# control.net
KiCad netlist of a schematic drawn in EAGLE
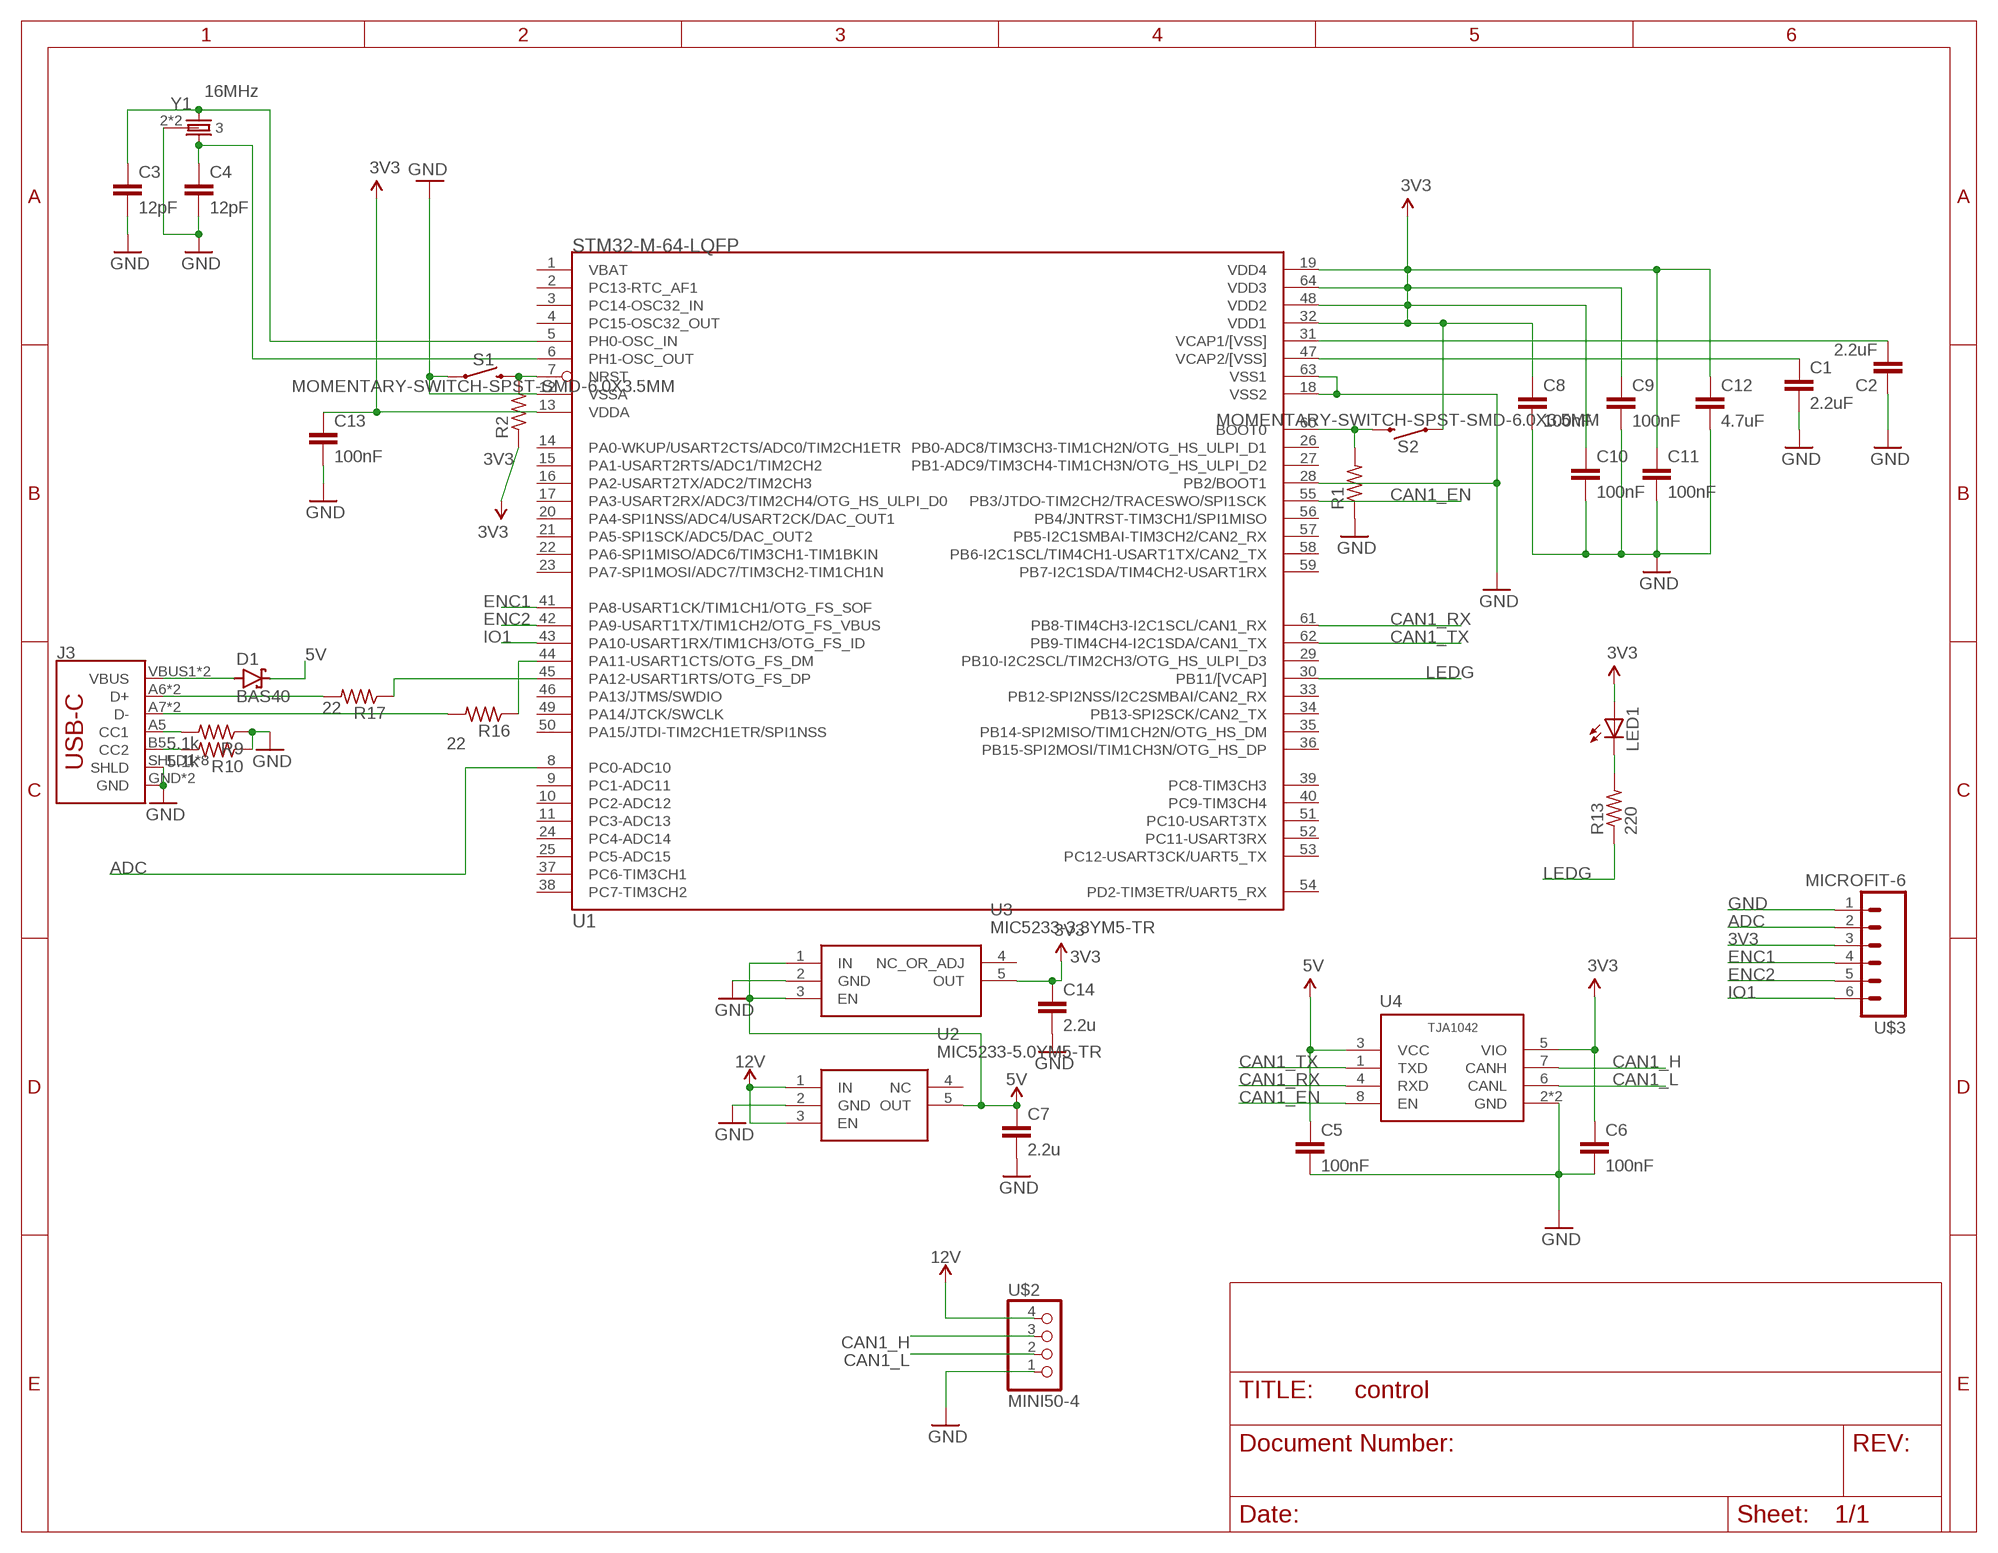
[diagram p0: schematic, sheet 1]

(export (version "E")
  (design (tool "Eeschema 10.0.6"))
  (components
    (comp (ref "C1")
      (value "2.2uF")
      (footprint "eagle-import:0603-C")
      (libsource (lib "eagle-import") (part "C0603"))
    )
    (comp (ref "C2")
      (value "2.2uF")
      (footprint "eagle-import:0603-C")
      (libsource (lib "eagle-import") (part "C0603"))
    )
    (comp (ref "C3")
      (value "12pF")
      (footprint "eagle-import:0603-C")
      (libsource (lib "eagle-import") (part "C0603"))
    )
    (comp (ref "C4")
      (value "12pF")
      (footprint "eagle-import:0603-C")
      (libsource (lib "eagle-import") (part "C0603"))
    )
    (comp (ref "C5")
      (value "100nF")
      (footprint "eagle-import:0603-C")
      (libsource (lib "eagle-import") (part "C0603"))
    )
    (comp (ref "C6")
      (value "100nF")
      (footprint "eagle-import:0603-C")
      (libsource (lib "eagle-import") (part "C0603"))
    )
    (comp (ref "C7")
      (value "2.2u")
      (footprint "eagle-import:C0603")
      (libsource (lib "eagle-import") (part "C-EUC0603"))
    )
    (comp (ref "C8")
      (value "100nF")
      (footprint "eagle-import:0603-C")
      (libsource (lib "eagle-import") (part "C0603"))
    )
    (comp (ref "C9")
      (value "100nF")
      (footprint "eagle-import:0603-C")
      (libsource (lib "eagle-import") (part "C0603"))
    )
    (comp (ref "C10")
      (value "100nF")
      (footprint "eagle-import:0603-C")
      (libsource (lib "eagle-import") (part "C0603"))
    )
    (comp (ref "C11")
      (value "100nF")
      (footprint "eagle-import:0603-C")
      (libsource (lib "eagle-import") (part "C0603"))
    )
    (comp (ref "C12")
      (value "4.7uF")
      (footprint "eagle-import:0603-C")
      (libsource (lib "eagle-import") (part "C0603"))
    )
    (comp (ref "C13")
      (value "100nF")
      (footprint "eagle-import:0603-C")
      (libsource (lib "eagle-import") (part "C0603"))
    )
    (comp (ref "C14")
      (value "2.2u")
      (footprint "eagle-import:C0603")
      (libsource (lib "eagle-import") (part "C-EUC0603"))
    )
    (comp (ref "D1")
      (value "BAS40")
      (footprint "eagle-import:SOT23")
      (libsource (lib "eagle-import") (part "BAS40"))
    )
    (comp (ref "J3")
      (value "USB-C-BREAKOUT_SPARKFUN-CONNECTORS_USB_C16PIN")
      (footprint "eagle-import:USB-C-BREAKOUT_SPARKFUN-CONNECTORS_USB-C-16P")
      (libsource (lib "eagle-import") (part "USB-C-BREAKOUT_SPARKFUN-CONNECTORS_USB_C16PIN"))
    )
    (comp (ref "LED1")
      (value "LEDCHIPLED_0805")
      (footprint "eagle-import:CHIPLED_0805")
      (libsource (lib "eagle-import") (part "LEDCHIPLED_0805"))
    )
    (comp (ref "R1")
      (value "R0402")
      (footprint "eagle-import:0402-R")
      (libsource (lib "eagle-import") (part "R0402"))
    )
    (comp (ref "R2")
      (value "R0402")
      (footprint "eagle-import:0402-R")
      (libsource (lib "eagle-import") (part "R0402"))
    )
    (comp (ref "R9")
      (value "5.1k")
      (footprint "eagle-import:0402-R")
      (libsource (lib "eagle-import") (part "R0402"))
    )
    (comp (ref "R10")
      (value "5.1k")
      (footprint "eagle-import:0402-R")
      (libsource (lib "eagle-import") (part "R0402"))
    )
    (comp (ref "R13")
      (value "220")
      (footprint "eagle-import:0402-R")
      (libsource (lib "eagle-import") (part "R0402"))
    )
    (comp (ref "R16")
      (value "22")
      (footprint "eagle-import:0402-R")
      (libsource (lib "eagle-import") (part "R0402"))
    )
    (comp (ref "R17")
      (value "22")
      (footprint "eagle-import:0402-R")
      (libsource (lib "eagle-import") (part "R0402"))
    )
    (comp (ref "S1")
      (value "MOMENTARY-SWITCH-SPST-SMD-6.0X3.5MM")
      (footprint "eagle-import:TACTILE_SWITCH_SMD_6.0X3.5MM")
      (libsource (lib "eagle-import") (part "MOMENTARY-SWITCH-SPST-SMD-6.0X3.5MM"))
    )
    (comp (ref "S2")
      (value "MOMENTARY-SWITCH-SPST-SMD-6.0X3.5MM")
      (footprint "eagle-import:TACTILE_SWITCH_SMD_6.0X3.5MM")
      (libsource (lib "eagle-import") (part "MOMENTARY-SWITCH-SPST-SMD-6.0X3.5MM"))
    )
    (comp (ref "U$2")
      (value "MINI50-4")
      (footprint "eagle-import:MINI50")
      (libsource (lib "eagle-import") (part "MINI50-4"))
    )
    (comp (ref "U$3")
      (value "MICROFIT-6")
      (footprint "eagle-import:MICROFIT-6")
      (libsource (lib "eagle-import") (part "MICROFIT-6"))
    )
    (comp (ref "U1")
      (value "STM32-M-64-LQFP")
      (footprint "eagle-import:LQFP64")
      (libsource (lib "eagle-import") (part "STM32-M-64-LQFP"))
    )
    (comp (ref "U2")
      (value "MIC5233-5.0YM5-TR")
      (footprint "eagle-import:SOT95P280X145-5N")
      (fields (field (name "MOUSER_PART_NUMBER") "998-MIC5233-5.0YM5TR"))
      (libsource (lib "eagle-import") (part "MIC5233-5.0YM5-TR"))
    )
    (comp (ref "U3")
      (value "MIC5233-3.3YM5-TR")
      (footprint "eagle-import:SOT95P280X145-5N")
      (fields (field (name "MOUSER_PART_NUMBER") "998-MIC5233-3.3YM5TR"))
      (libsource (lib "eagle-import") (part "MIC5233-3.3YM5-TR"))
    )
    (comp (ref "U4")
      (value "TJA1042HVSON")
      (footprint "eagle-import:HVSON8")
      (libsource (lib "eagle-import") (part "TJA1042HVSON"))
    )
    (comp (ref "Y1")
      (value "16MHz")
      (footprint "eagle-import:XTAL-3.2X2.5")
      (libsource (lib "eagle-import") (part "CRYSTAL-3.2X2.54-PIN"))
    )
  )
  (nets
    (net (code "1") (name "/ADC") (class "Default")
      (node (ref "U$3") (pin "2") (pinfunction "2_2") (pintype "passive"))
      (node (ref "U1") (pin "8") (pinfunction "PC0-ADC10_8") (pintype "bidirectional"))
    )
    (net (code "2") (name "/CAN1_EN") (class "Default")
      (node (ref "U1") (pin "55") (pinfunction "PB3/JTDO-TIM2CH2/TRACESWO/SPI1SCK_55") (pintype "bidirectional"))
      (node (ref "U4") (pin "8") (pinfunction "EN_8") (pintype "bidirectional"))
    )
    (net (code "3") (name "/CAN1_H") (class "Default")
      (node (ref "U$2") (pin "3") (pinfunction "2_3") (pintype "passive"))
      (node (ref "U4") (pin "7") (pinfunction "CANH_7") (pintype "bidirectional"))
    )
    (net (code "4") (name "/CAN1_L") (class "Default")
      (node (ref "U$2") (pin "2") (pinfunction "3_2") (pintype "passive"))
      (node (ref "U4") (pin "6") (pinfunction "CANL_6") (pintype "bidirectional"))
    )
    (net (code "5") (name "/CAN1_RX") (class "Default")
      (node (ref "U1") (pin "61") (pinfunction "PB8-TIM4CH3-I2C1SCL/CAN1_RX_61") (pintype "bidirectional"))
      (node (ref "U4") (pin "4") (pinfunction "RXD_4") (pintype "bidirectional"))
    )
    (net (code "6") (name "/CAN1_TX") (class "Default")
      (node (ref "U1") (pin "62") (pinfunction "PB9-TIM4CH4-I2C1SDA/CAN1_TX_62") (pintype "bidirectional"))
      (node (ref "U4") (pin "1") (pinfunction "TXD_1") (pintype "bidirectional"))
    )
    (net (code "7") (name "/ENC1") (class "Default")
      (node (ref "U$3") (pin "4") (pinfunction "4_4") (pintype "passive"))
      (node (ref "U1") (pin "41") (pinfunction "PA8-USART1CK/TIM1CH1/OTG_FS_SOF_41") (pintype "bidirectional"))
    )
    (net (code "8") (name "/ENC2") (class "Default")
      (node (ref "U$3") (pin "5") (pinfunction "5_5") (pintype "passive"))
      (node (ref "U1") (pin "42") (pinfunction "PA9-USART1TX/TIM1CH2/OTG_FS_VBUS_42") (pintype "bidirectional"))
    )
    (net (code "9") (name "/IO1") (class "Default")
      (node (ref "U$3") (pin "6") (pinfunction "6_6") (pintype "passive"))
      (node (ref "U1") (pin "43") (pinfunction "PA10-USART1RX/TIM1CH3/OTG_FS_ID_43") (pintype "bidirectional"))
    )
    (net (code "10") (name "/LEDG") (class "Default")
      (node (ref "R13") (pin "1") (pinfunction "1_1") (pintype "passive"))
      (node (ref "U1") (pin "30") (pinfunction "PB11/[VCAP]_30") (pintype "bidirectional"))
    )
    (net (code "11") (name "/VBAT") (class "Default")
      (node (ref "U1") (pin "1") (pinfunction "VBAT_1") (pintype "power_in"))
    )
    (net (code "12") (name "3V3") (class "Default")
      (node (ref "C10") (pin "1") (pinfunction "1_1") (pintype "passive"))
      (node (ref "C11") (pin "1") (pinfunction "1_1") (pintype "passive"))
      (node (ref "C12") (pin "1") (pinfunction "1_1") (pintype "passive"))
      (node (ref "C13") (pin "1") (pinfunction "1_1") (pintype "passive"))
      (node (ref "C14") (pin "1") (pinfunction "1_1") (pintype "passive"))
      (node (ref "C6") (pin "1") (pinfunction "1_1") (pintype "passive"))
      (node (ref "C8") (pin "1") (pinfunction "1_1") (pintype "passive"))
      (node (ref "C9") (pin "1") (pinfunction "1_1") (pintype "passive"))
      (node (ref "LED1") (pin "A") (pinfunction "A_A") (pintype "passive"))
      (node (ref "R2") (pin "1") (pinfunction "1_1") (pintype "passive"))
      (node (ref "S2") (pin "1") (pinfunction "1_1") (pintype "passive"))
      (node (ref "U$3") (pin "3") (pinfunction "3_3") (pintype "passive"))
      (node (ref "U1") (pin "13") (pinfunction "VDDA_13") (pintype "power_in"))
      (node (ref "U1") (pin "19") (pinfunction "VDD4_19") (pintype "bidirectional"))
      (node (ref "U1") (pin "32") (pinfunction "VDD1_32") (pintype "power_in"))
      (node (ref "U1") (pin "48") (pinfunction "VDD2_48") (pintype "power_in"))
      (node (ref "U1") (pin "64") (pinfunction "VDD3_64") (pintype "power_in"))
      (node (ref "U3") (pin "5") (pinfunction "OUT_5") (pintype "bidirectional"))
      (node (ref "U4") (pin "5") (pinfunction "VIO_5") (pintype "bidirectional"))
    )
    (net (code "13") (name "5V") (class "Default")
      (node (ref "C5") (pin "1") (pinfunction "1_1") (pintype "passive"))
      (node (ref "C7") (pin "1") (pinfunction "1_1") (pintype "passive"))
      (node (ref "D1") (pin "3") (pinfunction "C_3") (pintype "passive"))
      (node (ref "U2") (pin "5") (pinfunction "OUT_5") (pintype "bidirectional"))
      (node (ref "U3") (pin "1") (pinfunction "IN_1") (pintype "bidirectional"))
      (node (ref "U3") (pin "3") (pinfunction "EN_3") (pintype "bidirectional"))
      (node (ref "U4") (pin "3") (pinfunction "VCC_3") (pintype "bidirectional"))
    )
    (net (code "14") (name "12V") (class "Default")
      (node (ref "U$2") (pin "4") (pinfunction "1_4") (pintype "passive"))
      (node (ref "U2") (pin "1") (pinfunction "IN_1") (pintype "bidirectional"))
      (node (ref "U2") (pin "3") (pinfunction "EN_3") (pintype "bidirectional"))
    )
    (net (code "15") (name "GND") (class "Default")
      (node (ref "C1") (pin "2") (pinfunction "2_2") (pintype "passive"))
      (node (ref "C10") (pin "2") (pinfunction "2_2") (pintype "passive"))
      (node (ref "C11") (pin "2") (pinfunction "2_2") (pintype "passive"))
      (node (ref "C12") (pin "2") (pinfunction "2_2") (pintype "passive"))
      (node (ref "C13") (pin "2") (pinfunction "2_2") (pintype "passive"))
      (node (ref "C14") (pin "2") (pinfunction "2_2") (pintype "passive"))
      (node (ref "C2") (pin "1") (pinfunction "1_1") (pintype "passive"))
      (node (ref "C3") (pin "2") (pinfunction "2_2") (pintype "passive"))
      (node (ref "C4") (pin "2") (pinfunction "2_2") (pintype "passive"))
      (node (ref "C5") (pin "2") (pinfunction "2_2") (pintype "passive"))
      (node (ref "C6") (pin "2") (pinfunction "2_2") (pintype "passive"))
      (node (ref "C7") (pin "2") (pinfunction "2_2") (pintype "passive"))
      (node (ref "C8") (pin "2") (pinfunction "2_2") (pintype "passive"))
      (node (ref "C9") (pin "2") (pinfunction "2_2") (pintype "passive"))
      (node (ref "J3") (pin "GND") (pinfunction "GND_GND") (pintype "bidirectional"))
      (node (ref "J3") (pin "GND2") (pinfunction "GND_GND2") (pintype "bidirectional"))
      (node (ref "J3") (pin "SHLD1") (pinfunction "SHLD_SHLD1") (pintype "bidirectional"))
      (node (ref "J3") (pin "SHLD2") (pinfunction "SHLD_SHLD2") (pintype "bidirectional"))
      (node (ref "J3") (pin "SHLD3") (pinfunction "SHLD_SHLD3") (pintype "bidirectional"))
      (node (ref "J3") (pin "SHLD4") (pinfunction "SHLD_SHLD4") (pintype "bidirectional"))
      (node (ref "J3") (pin "SHLD5") (pinfunction "SHLD_SHLD5") (pintype "bidirectional"))
      (node (ref "J3") (pin "SHLD6") (pinfunction "SHLD_SHLD6") (pintype "bidirectional"))
      (node (ref "J3") (pin "SHLD7") (pinfunction "SHLD_SHLD7") (pintype "bidirectional"))
      (node (ref "J3") (pin "SHLD8") (pinfunction "SHLD_SHLD8") (pintype "bidirectional"))
      (node (ref "R1") (pin "1") (pinfunction "1_1") (pintype "passive"))
      (node (ref "R10") (pin "1") (pinfunction "1_1") (pintype "passive"))
      (node (ref "R9") (pin "1") (pinfunction "1_1") (pintype "passive"))
      (node (ref "S1") (pin "1") (pinfunction "1_1") (pintype "passive"))
      (node (ref "U$2") (pin "1") (pinfunction "4_1") (pintype "passive"))
      (node (ref "U$3") (pin "1") (pinfunction "1_1") (pintype "passive"))
      (node (ref "U1") (pin "12") (pinfunction "VSSA_12") (pintype "power_in"))
      (node (ref "U1") (pin "18") (pinfunction "VSS2_18") (pintype "bidirectional"))
      (node (ref "U1") (pin "28") (pinfunction "PB2/BOOT1_28") (pintype "bidirectional"))
      (node (ref "U1") (pin "63") (pinfunction "VSS1_63") (pintype "power_in"))
      (node (ref "U2") (pin "2") (pinfunction "GND_2") (pintype "bidirectional"))
      (node (ref "U3") (pin "2") (pinfunction "GND_2") (pintype "bidirectional"))
      (node (ref "U4") (pin "2") (pinfunction "GND_2") (pintype "bidirectional"))
      (node (ref "U4") (pin "PAD") (pinfunction "GND_PAD") (pintype "bidirectional"))
      (node (ref "Y1") (pin "2") (pinfunction "3_2") (pintype "bidirectional"))
      (node (ref "Y1") (pin "4") (pinfunction "3_4") (pintype "bidirectional"))
    )
    (net (code "16") (name "Net-(D1-A)") (class "Default")
      (node (ref "D1") (pin "1") (pinfunction "A_1") (pintype "passive"))
      (node (ref "J3") (pin "VBUS1") (pinfunction "VBUS_VBUS1") (pintype "bidirectional"))
      (node (ref "J3") (pin "VBUS2") (pinfunction "VBUS_VBUS2") (pintype "bidirectional"))
    )
    (net (code "17") (name "Net-(J3-CC1)") (class "Default")
      (node (ref "J3") (pin "A5") (pinfunction "CC1_A5") (pintype "bidirectional"))
      (node (ref "R9") (pin "2") (pinfunction "2_2") (pintype "passive"))
    )
    (net (code "18") (name "Net-(J3-CC2)") (class "Default")
      (node (ref "J3") (pin "B5") (pinfunction "CC2_B5") (pintype "bidirectional"))
      (node (ref "R10") (pin "2") (pinfunction "2_2") (pintype "passive"))
    )
    (net (code "19") (name "Net-(J3-D+-PadA6)") (class "Default")
      (node (ref "J3") (pin "A6") (pinfunction "D+_A6") (pintype "bidirectional"))
      (node (ref "J3") (pin "B6") (pinfunction "D+_B6") (pintype "bidirectional"))
      (node (ref "R17") (pin "2") (pinfunction "2_2") (pintype "passive"))
    )
    (net (code "20") (name "Net-(J3-D--PadA7)") (class "Default")
      (node (ref "J3") (pin "A7") (pinfunction "D-_A7") (pintype "bidirectional"))
      (node (ref "J3") (pin "B7") (pinfunction "D-_B7") (pintype "bidirectional"))
      (node (ref "R16") (pin "2") (pinfunction "2_2") (pintype "passive"))
    )
    (net (code "21") (name "Net-(LED1-PadC)") (class "Default")
      (node (ref "LED1") (pin "C") (pinfunction "C_C") (pintype "passive"))
      (node (ref "R13") (pin "2") (pinfunction "2_2") (pintype "passive"))
    )
    (net (code "22") (name "Net-(U1-BOOT0)") (class "Default")
      (node (ref "R1") (pin "2") (pinfunction "2_2") (pintype "passive"))
      (node (ref "S2") (pin "2") (pinfunction "2_2") (pintype "passive"))
      (node (ref "U1") (pin "60") (pinfunction "BOOT0_60") (pintype "input"))
    )
    (net (code "23") (name "Net-(U1-NRST)") (class "Default")
      (node (ref "R2") (pin "2") (pinfunction "2_2") (pintype "passive"))
      (node (ref "S1") (pin "2") (pinfunction "2_2") (pintype "passive"))
      (node (ref "U1") (pin "7") (pinfunction "NRST_7") (pintype "bidirectional"))
    )
    (net (code "24") (name "Net-(U1-PA11-USART1CTS{slash}OTG_FS_DM)") (class "Default")
      (node (ref "R16") (pin "1") (pinfunction "1_1") (pintype "passive"))
      (node (ref "U1") (pin "44") (pinfunction "PA11-USART1CTS/OTG_FS_DM_44") (pintype "bidirectional"))
    )
    (net (code "25") (name "Net-(U1-PA12-USART1RTS{slash}OTG_FS_DP)") (class "Default")
      (node (ref "R17") (pin "1") (pinfunction "1_1") (pintype "passive"))
      (node (ref "U1") (pin "45") (pinfunction "PA12-USART1RTS/OTG_FS_DP_45") (pintype "bidirectional"))
    )
    (net (code "26") (name "Net-(U1-PH0-OSC_IN)") (class "Default")
      (node (ref "C3") (pin "1") (pinfunction "1_1") (pintype "passive"))
      (node (ref "U1") (pin "5") (pinfunction "PH0-OSC_IN_5") (pintype "input"))
      (node (ref "Y1") (pin "1") (pinfunction "1_1") (pintype "passive"))
    )
    (net (code "27") (name "Net-(U1-PH1-OSC_OUT)") (class "Default")
      (node (ref "C4") (pin "1") (pinfunction "1_1") (pintype "passive"))
      (node (ref "U1") (pin "6") (pinfunction "PH1-OSC_OUT_6") (pintype "output"))
      (node (ref "Y1") (pin "3") (pinfunction "2_3") (pintype "passive"))
    )
    (net (code "28") (name "Net-(U1-VCAP1{slash}[VSS])") (class "Default")
      (node (ref "C2") (pin "2") (pinfunction "2_2") (pintype "passive"))
      (node (ref "U1") (pin "31") (pinfunction "VCAP1/[VSS]_31") (pintype "power_in"))
    )
    (net (code "29") (name "Net-(U1-VCAP2{slash}[VSS])") (class "Default")
      (node (ref "C1") (pin "1") (pinfunction "1_1") (pintype "passive"))
      (node (ref "U1") (pin "47") (pinfunction "VCAP2/[VSS]_47") (pintype "power_in"))
    )
    (net (code "30") (name "unconnected-(U1-PA0-WKUP{slash}USART2CTS{slash}ADC0{slash}TIM2CH1ETR-Pad14)") (class "Default")
      (node (ref "U1") (pin "14") (pinfunction "PA0-WKUP/USART2CTS/ADC0/TIM2CH1ETR_14") (pintype "bidirectional"))
    )
    (net (code "31") (name "unconnected-(U1-PA1-USART2RTS{slash}ADC1{slash}TIM2CH2-Pad15)") (class "Default")
      (node (ref "U1") (pin "15") (pinfunction "PA1-USART2RTS/ADC1/TIM2CH2_15") (pintype "bidirectional"))
    )
    (net (code "32") (name "unconnected-(U1-PA2-USART2TX{slash}ADC2{slash}TIM2CH3-Pad16)") (class "Default")
      (node (ref "U1") (pin "16") (pinfunction "PA2-USART2TX/ADC2/TIM2CH3_16") (pintype "bidirectional"))
    )
    (net (code "33") (name "unconnected-(U1-PA3-USART2RX{slash}ADC3{slash}TIM2CH4{slash}OTG_HS_ULPI_D0-Pad17)") (class "Default")
      (node (ref "U1") (pin "17") (pinfunction "PA3-USART2RX/ADC3/TIM2CH4/OTG_HS_ULPI_D0_17") (pintype "bidirectional"))
    )
    (net (code "34") (name "unconnected-(U1-PA4-SPI1NSS{slash}ADC4{slash}USART2CK{slash}DAC_OUT1-Pad20)") (class "Default")
      (node (ref "U1") (pin "20") (pinfunction "PA4-SPI1NSS/ADC4/USART2CK/DAC_OUT1_20") (pintype "bidirectional"))
    )
    (net (code "35") (name "unconnected-(U1-PA5-SPI1SCK{slash}ADC5{slash}DAC_OUT2-Pad21)") (class "Default")
      (node (ref "U1") (pin "21") (pinfunction "PA5-SPI1SCK/ADC5/DAC_OUT2_21") (pintype "bidirectional"))
    )
    (net (code "36") (name "unconnected-(U1-PA6-SPI1MISO{slash}ADC6{slash}TIM3CH1-TIM1BKIN-Pad22)") (class "Default")
      (node (ref "U1") (pin "22") (pinfunction "PA6-SPI1MISO/ADC6/TIM3CH1-TIM1BKIN_22") (pintype "bidirectional"))
    )
    (net (code "37") (name "unconnected-(U1-PA7-SPI1MOSI{slash}ADC7{slash}TIM3CH2-TIM1CH1N-Pad23)") (class "Default")
      (node (ref "U1") (pin "23") (pinfunction "PA7-SPI1MOSI/ADC7/TIM3CH2-TIM1CH1N_23") (pintype "bidirectional"))
    )
    (net (code "38") (name "unconnected-(U1-PA13{slash}JTMS{slash}SWDIO-Pad46)") (class "Default")
      (node (ref "U1") (pin "46") (pinfunction "PA13/JTMS/SWDIO_46") (pintype "bidirectional"))
    )
    (net (code "39") (name "unconnected-(U1-PA14{slash}JTCK{slash}SWCLK-Pad49)") (class "Default")
      (node (ref "U1") (pin "49") (pinfunction "PA14/JTCK/SWCLK_49") (pintype "bidirectional"))
    )
    (net (code "40") (name "unconnected-(U1-PA15{slash}JTDI-TIM2CH1ETR{slash}SPI1NSS-Pad50)") (class "Default")
      (node (ref "U1") (pin "50") (pinfunction "PA15/JTDI-TIM2CH1ETR/SPI1NSS_50") (pintype "bidirectional"))
    )
    (net (code "41") (name "unconnected-(U1-PB0-ADC8{slash}TIM3CH3-TIM1CH2N{slash}OTG_HS_ULPI_D1-Pad26)") (class "Default")
      (node (ref "U1") (pin "26") (pinfunction "PB0-ADC8/TIM3CH3-TIM1CH2N/OTG_HS_ULPI_D1_26") (pintype "bidirectional"))
    )
    (net (code "42") (name "unconnected-(U1-PB1-ADC9{slash}TIM3CH4-TIM1CH3N{slash}OTG_HS_ULPI_D2-Pad27)") (class "Default")
      (node (ref "U1") (pin "27") (pinfunction "PB1-ADC9/TIM3CH4-TIM1CH3N/OTG_HS_ULPI_D2_27") (pintype "bidirectional"))
    )
    (net (code "43") (name "unconnected-(U1-PB4{slash}JNTRST-TIM3CH1{slash}SPI1MISO-Pad56)") (class "Default")
      (node (ref "U1") (pin "56") (pinfunction "PB4/JNTRST-TIM3CH1/SPI1MISO_56") (pintype "bidirectional"))
    )
    (net (code "44") (name "unconnected-(U1-PB5-I2C1SMBAI-TIM3CH2{slash}CAN2_RX-Pad57)") (class "Default")
      (node (ref "U1") (pin "57") (pinfunction "PB5-I2C1SMBAI-TIM3CH2/CAN2_RX_57") (pintype "bidirectional"))
    )
    (net (code "45") (name "unconnected-(U1-PB6-I2C1SCL{slash}TIM4CH1-USART1TX{slash}CAN2_TX-Pad58)") (class "Default")
      (node (ref "U1") (pin "58") (pinfunction "PB6-I2C1SCL/TIM4CH1-USART1TX/CAN2_TX_58") (pintype "bidirectional"))
    )
    (net (code "46") (name "unconnected-(U1-PB7-I2C1SDA{slash}TIM4CH2-USART1RX-Pad59)") (class "Default")
      (node (ref "U1") (pin "59") (pinfunction "PB7-I2C1SDA/TIM4CH2-USART1RX_59") (pintype "bidirectional"))
    )
    (net (code "47") (name "unconnected-(U1-PB10-I2C2SCL{slash}TIM2CH3{slash}OTG_HS_ULPI_D3-Pad29)") (class "Default")
      (node (ref "U1") (pin "29") (pinfunction "PB10-I2C2SCL/TIM2CH3/OTG_HS_ULPI_D3_29") (pintype "bidirectional"))
    )
    (net (code "48") (name "unconnected-(U1-PB12-SPI2NSS{slash}I2C2SMBAI{slash}CAN2_RX-Pad33)") (class "Default")
      (node (ref "U1") (pin "33") (pinfunction "PB12-SPI2NSS/I2C2SMBAI/CAN2_RX_33") (pintype "bidirectional"))
    )
    (net (code "49") (name "unconnected-(U1-PB13-SPI2SCK{slash}CAN2_TX-Pad34)") (class "Default")
      (node (ref "U1") (pin "34") (pinfunction "PB13-SPI2SCK/CAN2_TX_34") (pintype "bidirectional"))
    )
    (net (code "50") (name "unconnected-(U1-PB14-SPI2MISO{slash}TIM1CH2N{slash}OTG_HS_DM-Pad35)") (class "Default")
      (node (ref "U1") (pin "35") (pinfunction "PB14-SPI2MISO/TIM1CH2N/OTG_HS_DM_35") (pintype "bidirectional"))
    )
    (net (code "51") (name "unconnected-(U1-PB15-SPI2MOSI{slash}TIM1CH3N{slash}OTG_HS_DP-Pad36)") (class "Default")
      (node (ref "U1") (pin "36") (pinfunction "PB15-SPI2MOSI/TIM1CH3N/OTG_HS_DP_36") (pintype "bidirectional"))
    )
    (net (code "52") (name "unconnected-(U1-PC1-ADC11-Pad9)") (class "Default")
      (node (ref "U1") (pin "9") (pinfunction "PC1-ADC11_9") (pintype "bidirectional"))
    )
    (net (code "53") (name "unconnected-(U1-PC2-ADC12-Pad10)") (class "Default")
      (node (ref "U1") (pin "10") (pinfunction "PC2-ADC12_10") (pintype "bidirectional"))
    )
    (net (code "54") (name "unconnected-(U1-PC3-ADC13-Pad11)") (class "Default")
      (node (ref "U1") (pin "11") (pinfunction "PC3-ADC13_11") (pintype "bidirectional"))
    )
    (net (code "55") (name "unconnected-(U1-PC4-ADC14-Pad24)") (class "Default")
      (node (ref "U1") (pin "24") (pinfunction "PC4-ADC14_24") (pintype "bidirectional"))
    )
    (net (code "56") (name "unconnected-(U1-PC5-ADC15-Pad25)") (class "Default")
      (node (ref "U1") (pin "25") (pinfunction "PC5-ADC15_25") (pintype "bidirectional"))
    )
    (net (code "57") (name "unconnected-(U1-PC6-TIM3CH1-Pad37)") (class "Default")
      (node (ref "U1") (pin "37") (pinfunction "PC6-TIM3CH1_37") (pintype "bidirectional"))
    )
    (net (code "58") (name "unconnected-(U1-PC7-TIM3CH2-Pad38)") (class "Default")
      (node (ref "U1") (pin "38") (pinfunction "PC7-TIM3CH2_38") (pintype "bidirectional"))
    )
    (net (code "59") (name "unconnected-(U1-PC8-TIM3CH3-Pad39)") (class "Default")
      (node (ref "U1") (pin "39") (pinfunction "PC8-TIM3CH3_39") (pintype "bidirectional"))
    )
    (net (code "60") (name "unconnected-(U1-PC9-TIM3CH4-Pad40)") (class "Default")
      (node (ref "U1") (pin "40") (pinfunction "PC9-TIM3CH4_40") (pintype "bidirectional"))
    )
    (net (code "61") (name "unconnected-(U1-PC10-USART3TX-Pad51)") (class "Default")
      (node (ref "U1") (pin "51") (pinfunction "PC10-USART3TX_51") (pintype "bidirectional"))
    )
    (net (code "62") (name "unconnected-(U1-PC11-USART3RX-Pad52)") (class "Default")
      (node (ref "U1") (pin "52") (pinfunction "PC11-USART3RX_52") (pintype "bidirectional"))
    )
    (net (code "63") (name "unconnected-(U1-PC12-USART3CK{slash}UART5_TX-Pad53)") (class "Default")
      (node (ref "U1") (pin "53") (pinfunction "PC12-USART3CK/UART5_TX_53") (pintype "bidirectional"))
    )
    (net (code "64") (name "unconnected-(U1-PC13-RTC_AF1-Pad2)") (class "Default")
      (node (ref "U1") (pin "2") (pinfunction "PC13-RTC_AF1_2") (pintype "bidirectional"))
    )
    (net (code "65") (name "unconnected-(U1-PC14-OSC32_IN-Pad3)") (class "Default")
      (node (ref "U1") (pin "3") (pinfunction "PC14-OSC32_IN_3") (pintype "bidirectional"))
    )
    (net (code "66") (name "unconnected-(U1-PC15-OSC32_OUT-Pad4)") (class "Default")
      (node (ref "U1") (pin "4") (pinfunction "PC15-OSC32_OUT_4") (pintype "bidirectional"))
    )
    (net (code "67") (name "unconnected-(U1-PD2-TIM3ETR{slash}UART5_RX-Pad54)") (class "Default")
      (node (ref "U1") (pin "54") (pinfunction "PD2-TIM3ETR/UART5_RX_54") (pintype "bidirectional"))
    )
    (net (code "68") (name "unconnected-(U2-NC-Pad4)") (class "Default")
      (node (ref "U2") (pin "4") (pinfunction "NC_4") (pintype "no_connect"))
    )
    (net (code "69") (name "unconnected-(U3-NC_OR_ADJ-Pad4)") (class "Default")
      (node (ref "U3") (pin "4") (pinfunction "NC_OR_ADJ_4") (pintype "bidirectional"))
    )
  )
)
